# micro_schematic.net
KiCad netlist of a schematic drawn in EAGLE
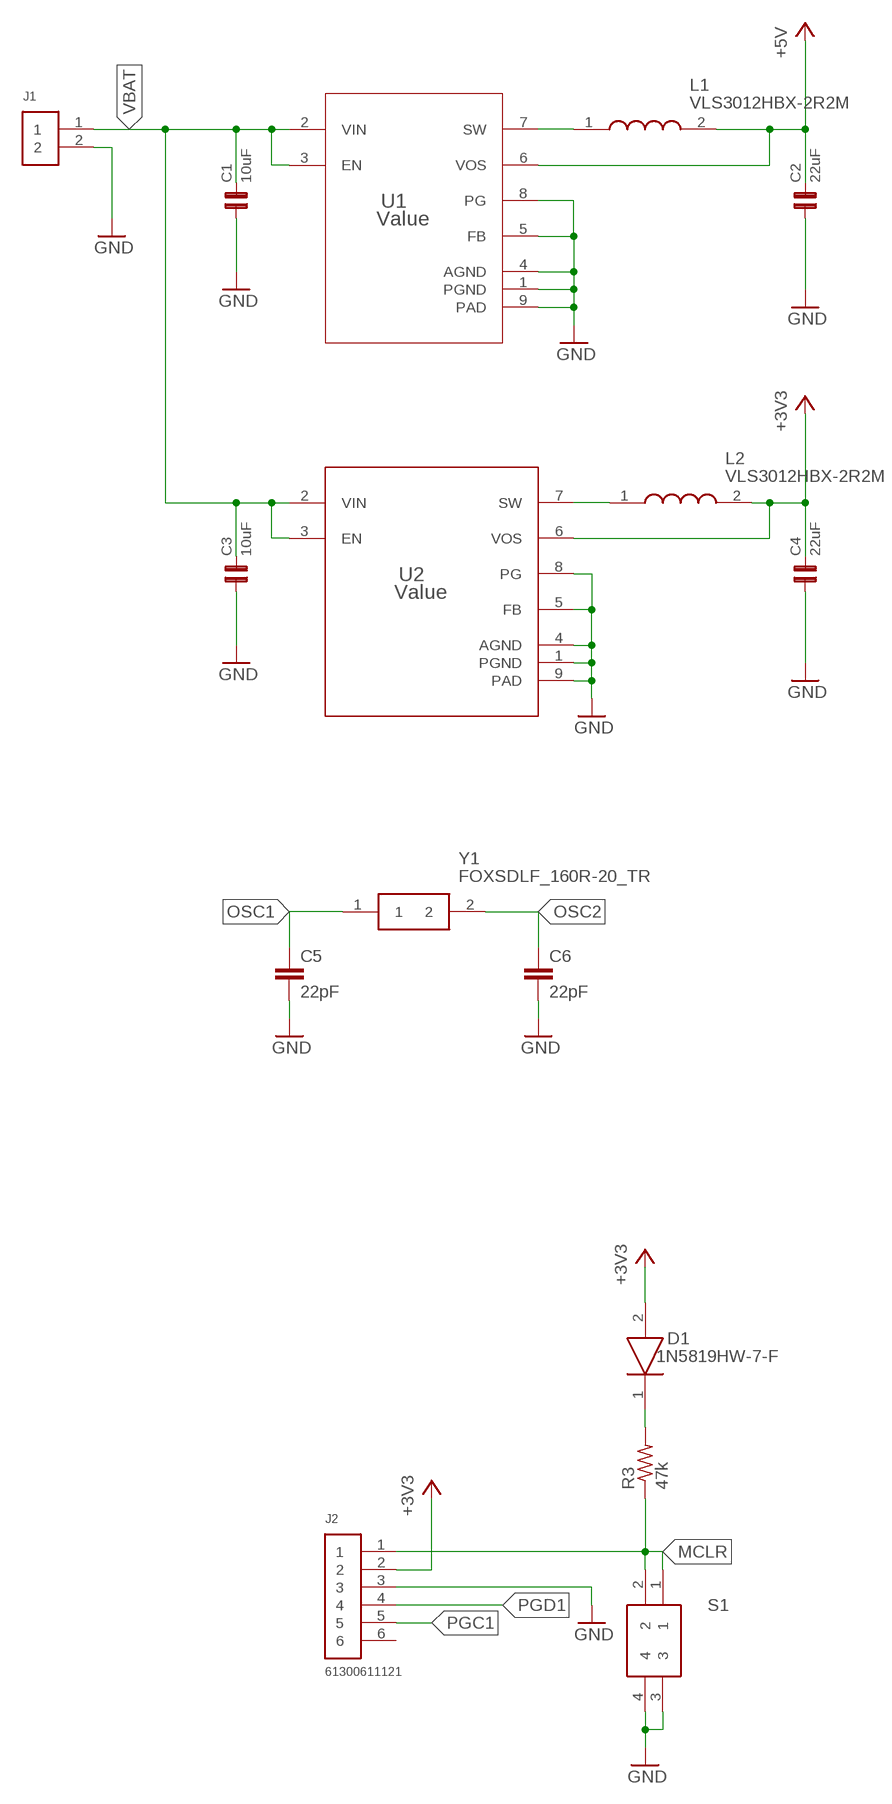
[diagram p0: schematic, sheet 1, part 1 of 2]
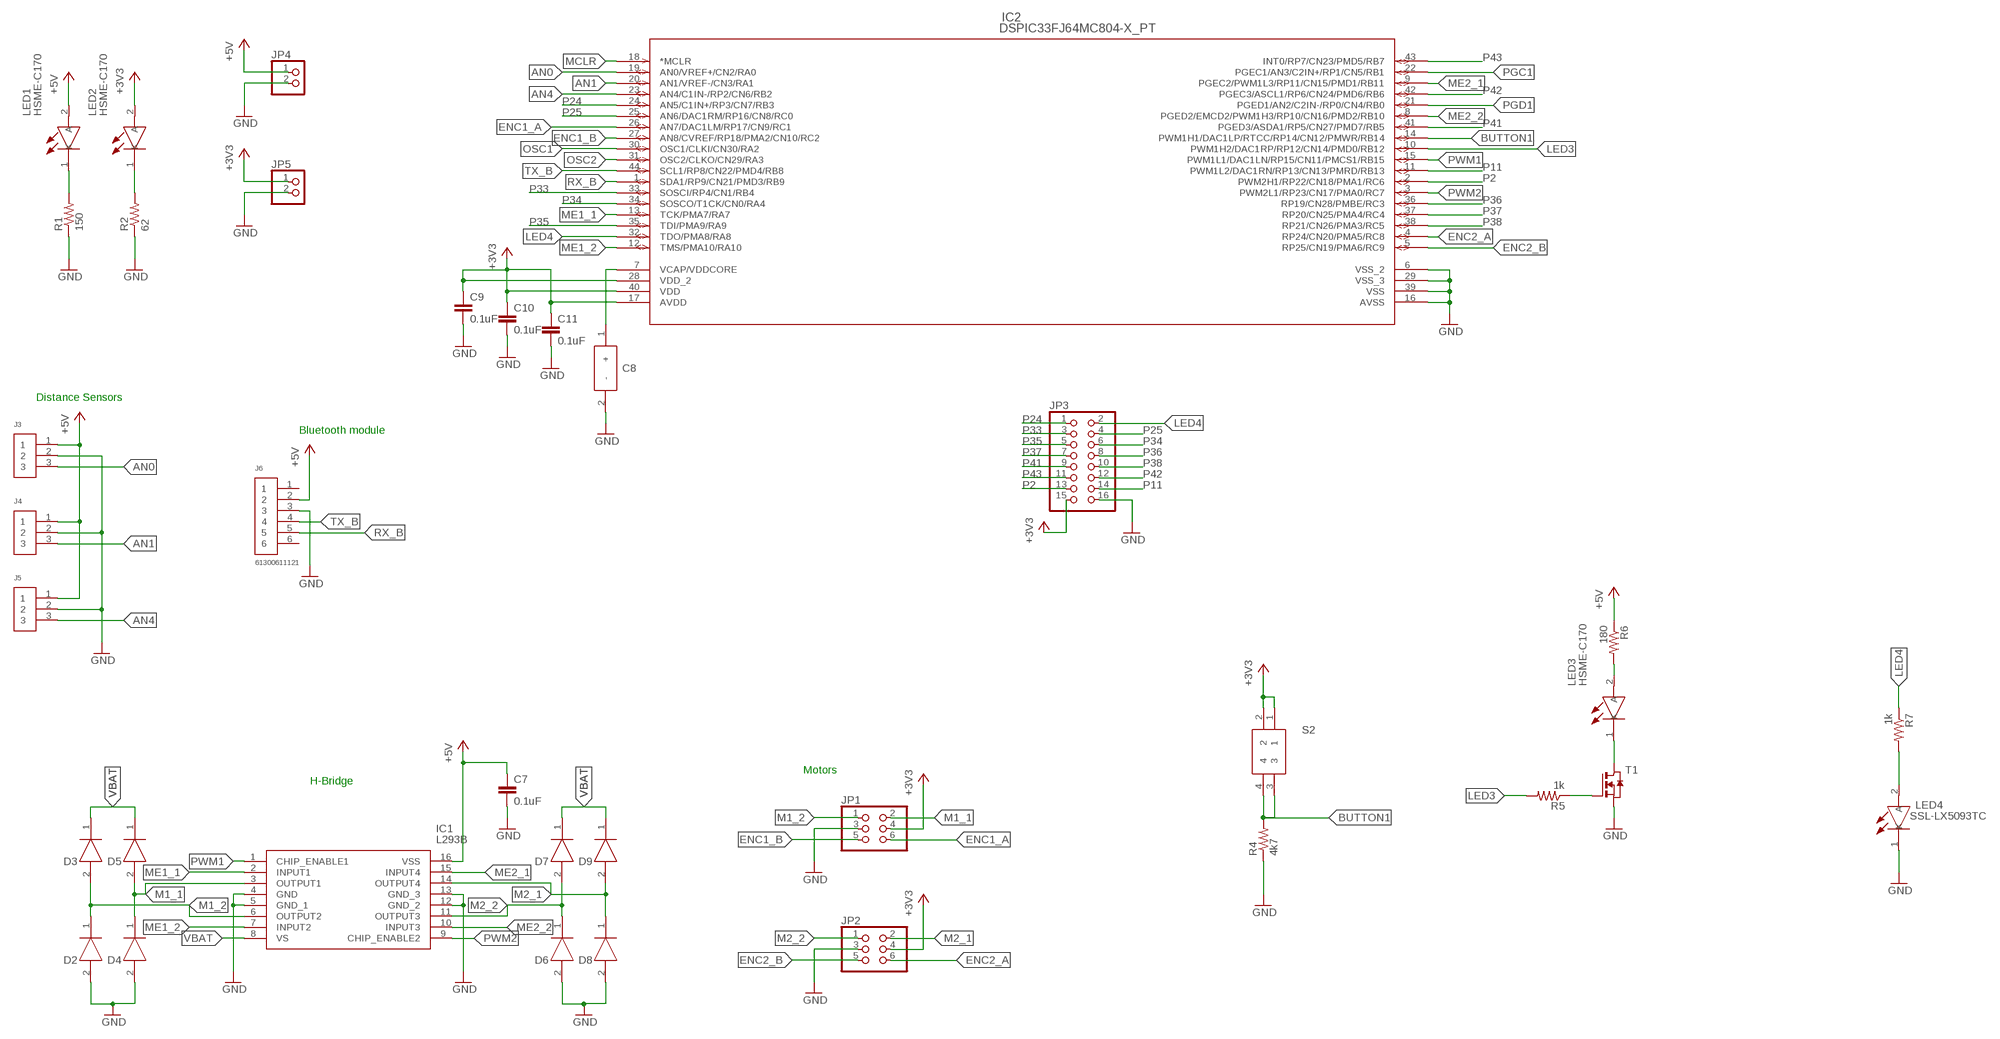
[diagram p1: schematic, sheet 1, part 2 of 2]

(export (version "E")
  (design (tool "Eeschema 10.0.6"))
  (components
    (comp (ref "C1")
      (value "10uF")
      (footprint "eagle-import:0805")
      (libsource (lib "eagle-import") (part "C0805"))
    )
    (comp (ref "C2")
      (value "22uF")
      (footprint "eagle-import:0805")
      (libsource (lib "eagle-import") (part "C0805"))
    )
    (comp (ref "C3")
      (value "10uF")
      (footprint "eagle-import:0805")
      (libsource (lib "eagle-import") (part "C0805"))
    )
    (comp (ref "C4")
      (value "22uF")
      (footprint "eagle-import:0805")
      (libsource (lib "eagle-import") (part "C0805"))
    )
    (comp (ref "C5")
      (value "22pF")
      (footprint "eagle-import:C0805")
      (libsource (lib "eagle-import") (part "C-EUC0805"))
    )
    (comp (ref "C6")
      (value "22pF")
      (footprint "eagle-import:C0805")
      (libsource (lib "eagle-import") (part "C-EUC0805"))
    )
    (comp (ref "C7")
      (value "0.1uF")
      (footprint "eagle-import:C0805")
      (libsource (lib "eagle-import") (part "C-EUC0805"))
    )
    (comp (ref "C8")
      (value "TPSB106K025T1800")
      (footprint "eagle-import:DIONM3528X210N")
      (fields (field (name "MOUSER_PART_NUMBER") "581-TPSB106K025T1800"))
      (libsource (lib "eagle-import") (part "TPSB106K025T1800"))
    )
    (comp (ref "C9")
      (value "0.1uF")
      (footprint "eagle-import:C0805")
      (libsource (lib "eagle-import") (part "C-EUC0805"))
    )
    (comp (ref "C10")
      (value "0.1uF")
      (footprint "eagle-import:C0805")
      (libsource (lib "eagle-import") (part "C-EUC0805"))
    )
    (comp (ref "C11")
      (value "0.1uF")
      (footprint "eagle-import:C0805")
      (libsource (lib "eagle-import") (part "C-EUC0805"))
    )
    (comp (ref "D1")
      (value "1N5819HW-7-F")
      (footprint "eagle-import:SOD3716X145N")
      (fields (field (name "MOUSER_PART_NUMBER") "621-1N5819HW-F"))
      (libsource (lib "eagle-import") (part "1N5819HW-7-F"))
    )
    (comp (ref "D2")
      (value "1N5819HW-7-F")
      (footprint "eagle-import:SOD3716X145N")
      (fields (field (name "MOUSER_PART_NUMBER") "621-1N5819HW-F"))
      (libsource (lib "eagle-import") (part "1N5819HW-7-F"))
    )
    (comp (ref "D3")
      (value "1N5819HW-7-F")
      (footprint "eagle-import:SOD3716X145N")
      (fields (field (name "MOUSER_PART_NUMBER") "621-1N5819HW-F"))
      (libsource (lib "eagle-import") (part "1N5819HW-7-F"))
    )
    (comp (ref "D4")
      (value "1N5819HW-7-F")
      (footprint "eagle-import:SOD3716X145N")
      (fields (field (name "MOUSER_PART_NUMBER") "621-1N5819HW-F"))
      (libsource (lib "eagle-import") (part "1N5819HW-7-F"))
    )
    (comp (ref "D5")
      (value "1N5819HW-7-F")
      (footprint "eagle-import:SOD3716X145N")
      (fields (field (name "MOUSER_PART_NUMBER") "621-1N5819HW-F"))
      (libsource (lib "eagle-import") (part "1N5819HW-7-F"))
    )
    (comp (ref "D6")
      (value "1N5819HW-7-F")
      (footprint "eagle-import:SOD3716X145N")
      (fields (field (name "MOUSER_PART_NUMBER") "621-1N5819HW-F"))
      (libsource (lib "eagle-import") (part "1N5819HW-7-F"))
    )
    (comp (ref "D7")
      (value "1N5819HW-7-F")
      (footprint "eagle-import:SOD3716X145N")
      (fields (field (name "MOUSER_PART_NUMBER") "621-1N5819HW-F"))
      (libsource (lib "eagle-import") (part "1N5819HW-7-F"))
    )
    (comp (ref "D8")
      (value "1N5819HW-7-F")
      (footprint "eagle-import:SOD3716X145N")
      (fields (field (name "MOUSER_PART_NUMBER") "621-1N5819HW-F"))
      (libsource (lib "eagle-import") (part "1N5819HW-7-F"))
    )
    (comp (ref "D9")
      (value "1N5819HW-7-F")
      (footprint "eagle-import:SOD3716X145N")
      (fields (field (name "MOUSER_PART_NUMBER") "621-1N5819HW-F"))
      (libsource (lib "eagle-import") (part "1N5819HW-7-F"))
    )
    (comp (ref "IC1")
      (value "L293B")
      (footprint "eagle-import:DIP780W50P254L2000H510Q16N")
      (fields (field (name "MOUSER_PART_NUMBER") "511-L293B"))
      (libsource (lib "eagle-import") (part "L293B"))
    )
    (comp (ref "IC2")
      (value "DSPIC33FJ64MC804-X_PT")
      (footprint "eagle-import:TQFP44_10X10MC")
      (libsource (lib "eagle-import") (part "DSPIC33FJ64MC804-X_PT"))
    )
    (comp (ref "J1")
      (value "61300211121")
      (footprint "eagle-import:61300211121")
      (fields
        (field (name "DIGI_KEY_PART_NUMBER") "732-5315-ND")
        (field (name "MANUFACTURER") "Wurth Electronics Inc.")
        (field (name "CREATED_BY") "PCBLayout.com")
      )
      (libsource (lib "eagle-import") (part "61300211121"))
    )
    (comp (ref "J2")
      (value "61300611121")
      (footprint "eagle-import:61300611121")
      (fields
        (field (name "DIGI_KEY_PART_NUMBER") "732-5319-ND")
        (field (name "MANUFACTURER") "Wurth Electronics Inc.")
        (field (name "CREATED_BY") "PCBLayout.com")
      )
      (libsource (lib "eagle-import") (part "61300611121"))
    )
    (comp (ref "J3")
      (value "61300311121")
      (footprint "eagle-import:61300311121")
      (fields
        (field (name "DIGI_KEY_PART_NUMBER") "732-5316-ND")
        (field (name "MANUFACTURER") "Wurth Electronics Inc.")
        (field (name "CREATED_BY") "PCBLayout.com")
      )
      (libsource (lib "eagle-import") (part "61300311121"))
    )
    (comp (ref "J4")
      (value "61300311121")
      (footprint "eagle-import:61300311121")
      (fields
        (field (name "DIGI_KEY_PART_NUMBER") "732-5316-ND")
        (field (name "MANUFACTURER") "Wurth Electronics Inc.")
        (field (name "CREATED_BY") "PCBLayout.com")
      )
      (libsource (lib "eagle-import") (part "61300311121"))
    )
    (comp (ref "J5")
      (value "61300311121")
      (footprint "eagle-import:61300311121")
      (fields
        (field (name "DIGI_KEY_PART_NUMBER") "732-5316-ND")
        (field (name "MANUFACTURER") "Wurth Electronics Inc.")
        (field (name "CREATED_BY") "PCBLayout.com")
      )
      (libsource (lib "eagle-import") (part "61300311121"))
    )
    (comp (ref "J6")
      (value "61300611121")
      (footprint "eagle-import:61300611121")
      (fields
        (field (name "DIGI_KEY_PART_NUMBER") "732-5319-ND")
        (field (name "MANUFACTURER") "Wurth Electronics Inc.")
        (field (name "CREATED_BY") "PCBLayout.com")
      )
      (libsource (lib "eagle-import") (part "61300611121"))
    )
    (comp (ref "JP1")
      (value "PINHD-2X3")
      (footprint "eagle-import:2X03")
      (libsource (lib "eagle-import") (part "PINHD-2X3"))
    )
    (comp (ref "JP2")
      (value "PINHD-2X3")
      (footprint "eagle-import:2X03")
      (libsource (lib "eagle-import") (part "PINHD-2X3"))
    )
    (comp (ref "JP3")
      (value "PINHD-2X8")
      (footprint "eagle-import:2X08")
      (libsource (lib "eagle-import") (part "PINHD-2X8"))
    )
    (comp (ref "JP4")
      (value "PINHD-1X2")
      (footprint "eagle-import:1X02")
      (libsource (lib "eagle-import") (part "PINHD-1X2"))
    )
    (comp (ref "JP5")
      (value "PINHD-1X2")
      (footprint "eagle-import:1X02")
      (libsource (lib "eagle-import") (part "PINHD-1X2"))
    )
    (comp (ref "L1")
      (value "VLS3012HBX-2R2M")
      (footprint "eagle-import:INDPM3030X120N")
      (fields (field (name "MOUSER_PART_NUMBER") "810-VLS3012HBX-2R2M"))
      (libsource (lib "eagle-import") (part "VLS3012HBX-2R2M"))
    )
    (comp (ref "L2")
      (value "VLS3012HBX-2R2M")
      (footprint "eagle-import:INDPM3030X120N")
      (fields (field (name "MOUSER_PART_NUMBER") "810-VLS3012HBX-2R2M"))
      (libsource (lib "eagle-import") (part "VLS3012HBX-2R2M"))
    )
    (comp (ref "LED1")
      (value "HSME-C170")
      (footprint "eagle-import:LEDC2012X90N")
      (fields (field (name "MOUSER_PART_NUMBER") "630-HSME-C170"))
      (libsource (lib "eagle-import") (part "HSME-C170"))
    )
    (comp (ref "LED2")
      (value "HSME-C170")
      (footprint "eagle-import:LEDC2012X90N")
      (fields (field (name "MOUSER_PART_NUMBER") "630-HSME-C170"))
      (libsource (lib "eagle-import") (part "HSME-C170"))
    )
    (comp (ref "LED3")
      (value "HSME-C170")
      (footprint "eagle-import:LEDC2012X90N")
      (fields (field (name "MOUSER_PART_NUMBER") "630-HSME-C170"))
      (libsource (lib "eagle-import") (part "HSME-C170"))
    )
    (comp (ref "LED4")
      (value "SSL-LX5093TC")
      (footprint "eagle-import:SSL-LX5093SGC_B")
      (fields (field (name "MOUSER_PART_NUMBER") "696-SSL-LX5093TC"))
      (libsource (lib "eagle-import") (part "SSL-LX5093TC"))
    )
    (comp (ref "R1")
      (value "150")
      (footprint "eagle-import:R0805")
      (libsource (lib "eagle-import") (part "R-US_R0805"))
    )
    (comp (ref "R2")
      (value "62")
      (footprint "eagle-import:R0805")
      (libsource (lib "eagle-import") (part "R-US_R0805"))
    )
    (comp (ref "R3")
      (value "47k")
      (footprint "eagle-import:R0805")
      (libsource (lib "eagle-import") (part "R-US_R0805"))
    )
    (comp (ref "R4")
      (value "4k7")
      (footprint "eagle-import:R0805")
      (libsource (lib "eagle-import") (part "R-US_R0805"))
    )
    (comp (ref "R5")
      (value "1k")
      (footprint "eagle-import:R0805")
      (libsource (lib "eagle-import") (part "R-US_R0805"))
    )
    (comp (ref "R6")
      (value "180")
      (footprint "eagle-import:R0805")
      (libsource (lib "eagle-import") (part "R-US_R0805"))
    )
    (comp (ref "R7")
      (value "1k")
      (footprint "eagle-import:R0805")
      (libsource (lib "eagle-import") (part "R-US_R0805"))
    )
    (comp (ref "S1")
      (value "PTS647SM50SMTR2LFS")
      (footprint "eagle-import:PTS647SM50SMTR2LFS")
      (fields (field (name "MOUSER_PART_NUMBER") "611-PTS647SM50SMTR2L"))
      (libsource (lib "eagle-import") (part "PTS647SM50SMTR2LFS"))
    )
    (comp (ref "S2")
      (value "PTS647SM50SMTR2LFS")
      (footprint "eagle-import:PTS647SM50SMTR2LFS")
      (fields (field (name "MOUSER_PART_NUMBER") "611-PTS647SM50SMTR2L"))
      (libsource (lib "eagle-import") (part "PTS647SM50SMTR2LFS"))
    )
    (comp (ref "T1")
      (value "NMOSSOT23")
      (footprint "eagle-import:SOT-23")
      (libsource (lib "eagle-import") (part "NMOSSOT23"))
    )
    (comp (ref "U1")
      (value "Value")
      (footprint "eagle-import:DSG0008A")
      (fields
        (field (name "ALTERNATEPARTNUMBER") "TPS62163DSGT")
        (field (name "MANUFACTURER") "Texas Instruments")
        (field (name "PARTNUMBER") "TPS62163DSGR")
        (field (name "SPICEPREFIX") "X")
      )
      (libsource (lib "eagle-import") (part "TPS62163DSGR"))
    )
    (comp (ref "U2")
      (value "Value")
      (footprint "eagle-import:DSG0008A")
      (fields (field (name "MANUFACTURER") "Texas Instruments") (field (name "PARTNUMBER") "TPS62162QDSGRQ1"))
      (libsource (lib "eagle-import") (part "TPS62162QDSGRQ1"))
    )
    (comp (ref "Y1")
      (value "FOXSDLF_160R-20_TR")
      (footprint "eagle-import:FOXSDLF_240F-20")
      (fields
        (field (name "MANUFACTURER_PART_NUMBER") "FOXSDLF/160R-20/TR")
        (field (name "MOUSER_PART_NUMBER") "559-FOXSDLF/160R-20")
      )
      (libsource (lib "eagle-import") (part "FOXSDLF_160R-20_TR"))
    )
  )
  (nets
    (net (code "1") (name "+3V3") (class "Default")
      (node (ref "C10") (pin "1") (pinfunction "1_1") (pintype "passive"))
      (node (ref "C11") (pin "1") (pinfunction "1_1") (pintype "passive"))
      (node (ref "C4") (pin "2") (pinfunction "2_2") (pintype "passive"))
      (node (ref "C9") (pin "1") (pinfunction "1_1") (pintype "passive"))
      (node (ref "D1") (pin "2") (pinfunction "A_2") (pintype "bidirectional"))
      (node (ref "IC2") (pin "17") (pinfunction "AVDD_17") (pintype "power_in"))
      (node (ref "IC2") (pin "28") (pinfunction "VDD_2_28") (pintype "power_in"))
      (node (ref "IC2") (pin "40") (pinfunction "VDD_40") (pintype "power_in"))
      (node (ref "J2") (pin "2") (pinfunction "2_2") (pintype "passive"))
      (node (ref "JP1") (pin "4") (pinfunction "4_4") (pintype "passive"))
      (node (ref "JP2") (pin "4") (pinfunction "4_4") (pintype "passive"))
      (node (ref "JP3") (pin "15") (pinfunction "15_15") (pintype "passive"))
      (node (ref "JP5") (pin "1") (pinfunction "1_1") (pintype "passive"))
      (node (ref "L2") (pin "2") (pinfunction "2_2") (pintype "bidirectional"))
      (node (ref "LED2") (pin "2") (pinfunction "A_2") (pintype "bidirectional"))
      (node (ref "S2") (pin "1") (pinfunction "1_1") (pintype "bidirectional"))
      (node (ref "S2") (pin "2") (pinfunction "2_2") (pintype "bidirectional"))
      (node (ref "U2") (pin "6") (pinfunction "VOS_6") (pintype "input"))
    )
    (net (code "2") (name "+5V") (class "Default")
      (node (ref "C2") (pin "2") (pinfunction "2_2") (pintype "passive"))
      (node (ref "C7") (pin "1") (pinfunction "1_1") (pintype "passive"))
      (node (ref "IC1") (pin "16") (pinfunction "VSS_16") (pintype "power_in"))
      (node (ref "J3") (pin "1") (pinfunction "1_1") (pintype "passive"))
      (node (ref "J4") (pin "1") (pinfunction "1_1") (pintype "passive"))
      (node (ref "J5") (pin "1") (pinfunction "1_1") (pintype "passive"))
      (node (ref "J6") (pin "2") (pinfunction "2_2") (pintype "passive"))
      (node (ref "JP4") (pin "1") (pinfunction "1_1") (pintype "passive"))
      (node (ref "L1") (pin "2") (pinfunction "2_2") (pintype "bidirectional"))
      (node (ref "LED1") (pin "2") (pinfunction "A_2") (pintype "bidirectional"))
      (node (ref "R6") (pin "1") (pinfunction "1_1") (pintype "passive"))
      (node (ref "U1") (pin "6") (pinfunction "VOS_6") (pintype "input"))
    )
    (net (code "3") (name "/P2") (class "Default")
      (node (ref "IC2") (pin "2") (pinfunction "PWM2H1/RP22/CN18/PMA1/RC6_2") (pintype "bidirectional"))
      (node (ref "JP3") (pin "13") (pinfunction "13_13") (pintype "passive"))
    )
    (net (code "4") (name "/P11") (class "Default")
      (node (ref "IC2") (pin "11") (pinfunction "PWM1L2/DAC1RN/RP13/CN13/PMRD/RB13_11") (pintype "bidirectional"))
      (node (ref "JP3") (pin "14") (pinfunction "14_14") (pintype "passive"))
    )
    (net (code "5") (name "/P24") (class "Default")
      (node (ref "IC2") (pin "24") (pinfunction "AN5/C1IN+/RP3/CN7/RB3_24") (pintype "bidirectional"))
      (node (ref "JP3") (pin "1") (pinfunction "1_1") (pintype "passive"))
    )
    (net (code "6") (name "/P25") (class "Default")
      (node (ref "IC2") (pin "25") (pinfunction "AN6/DAC1RM/RP16/CN8/RC0_25") (pintype "bidirectional"))
      (node (ref "JP3") (pin "4") (pinfunction "4_4") (pintype "passive"))
    )
    (net (code "7") (name "/P33") (class "Default")
      (node (ref "IC2") (pin "33") (pinfunction "SOSCI/RP4/CN1/RB4_33") (pintype "bidirectional"))
      (node (ref "JP3") (pin "3") (pinfunction "3_3") (pintype "passive"))
    )
    (net (code "8") (name "/P34") (class "Default")
      (node (ref "IC2") (pin "34") (pinfunction "SOSCO/T1CK/CN0/RA4_34") (pintype "bidirectional"))
      (node (ref "JP3") (pin "6") (pinfunction "6_6") (pintype "passive"))
    )
    (net (code "9") (name "/P35") (class "Default")
      (node (ref "IC2") (pin "35") (pinfunction "TDI/PMA9/RA9_35") (pintype "bidirectional"))
      (node (ref "JP3") (pin "5") (pinfunction "5_5") (pintype "passive"))
    )
    (net (code "10") (name "/P36") (class "Default")
      (node (ref "IC2") (pin "36") (pinfunction "RP19/CN28/PMBE/RC3_36") (pintype "bidirectional"))
      (node (ref "JP3") (pin "8") (pinfunction "8_8") (pintype "passive"))
    )
    (net (code "11") (name "/P37") (class "Default")
      (node (ref "IC2") (pin "37") (pinfunction "RP20/CN25/PMA4/RC4_37") (pintype "bidirectional"))
      (node (ref "JP3") (pin "7") (pinfunction "7_7") (pintype "passive"))
    )
    (net (code "12") (name "/P38") (class "Default")
      (node (ref "IC2") (pin "38") (pinfunction "RP21/CN26/PMA3/RC5_38") (pintype "bidirectional"))
      (node (ref "JP3") (pin "10") (pinfunction "10_10") (pintype "passive"))
    )
    (net (code "13") (name "/P41") (class "Default")
      (node (ref "IC2") (pin "41") (pinfunction "PGED3/ASDA1/RP5/CN27/PMD7/RB5_41") (pintype "bidirectional"))
      (node (ref "JP3") (pin "9") (pinfunction "9_9") (pintype "passive"))
    )
    (net (code "14") (name "/P42") (class "Default")
      (node (ref "IC2") (pin "42") (pinfunction "PGEC3/ASCL1/RP6/CN24/PMD6/RB6_42") (pintype "bidirectional"))
      (node (ref "JP3") (pin "12") (pinfunction "12_12") (pintype "passive"))
    )
    (net (code "15") (name "/P43") (class "Default")
      (node (ref "IC2") (pin "43") (pinfunction "INT0/RP7/CN23/PMD5/RB7_43") (pintype "bidirectional"))
      (node (ref "JP3") (pin "11") (pinfunction "11_11") (pintype "passive"))
    )
    (net (code "16") (name "AN0") (class "Default")
      (node (ref "IC2") (pin "19") (pinfunction "AN0/VREF+/CN2/RA0_19") (pintype "bidirectional"))
      (node (ref "J3") (pin "3") (pinfunction "3_3") (pintype "passive"))
    )
    (net (code "17") (name "AN1") (class "Default")
      (node (ref "IC2") (pin "20") (pinfunction "AN1/VREF-/CN3/RA1_20") (pintype "bidirectional"))
      (node (ref "J4") (pin "3") (pinfunction "3_3") (pintype "passive"))
    )
    (net (code "18") (name "AN4") (class "Default")
      (node (ref "IC2") (pin "23") (pinfunction "AN4/C1IN-/RP2/CN6/RB2_23") (pintype "bidirectional"))
      (node (ref "J5") (pin "3") (pinfunction "3_3") (pintype "passive"))
    )
    (net (code "19") (name "BUTTON1") (class "Default")
      (node (ref "IC2") (pin "14") (pinfunction "PWM1H1/DAC1LP/RTCC/RP14/CN12/PMWR/RB14_14") (pintype "bidirectional"))
      (node (ref "R4") (pin "2") (pinfunction "2_2") (pintype "passive"))
      (node (ref "S2") (pin "3") (pinfunction "3_3") (pintype "bidirectional"))
      (node (ref "S2") (pin "4") (pinfunction "4_4") (pintype "bidirectional"))
    )
    (net (code "20") (name "ENC1_A") (class "Default")
      (node (ref "IC2") (pin "26") (pinfunction "AN7/DAC1LM/RP17/CN9/RC1_26") (pintype "bidirectional"))
      (node (ref "JP1") (pin "6") (pinfunction "6_6") (pintype "passive"))
    )
    (net (code "21") (name "ENC1_B") (class "Default")
      (node (ref "IC2") (pin "27") (pinfunction "AN8/CVREF/RP18/PMA2/CN10/RC2_27") (pintype "bidirectional"))
      (node (ref "JP1") (pin "5") (pinfunction "5_5") (pintype "passive"))
    )
    (net (code "22") (name "ENC2_A") (class "Default")
      (node (ref "IC2") (pin "4") (pinfunction "RP24/CN20/PMA5/RC8_4") (pintype "bidirectional"))
      (node (ref "JP2") (pin "6") (pinfunction "6_6") (pintype "passive"))
    )
    (net (code "23") (name "ENC2_B") (class "Default")
      (node (ref "IC2") (pin "5") (pinfunction "RP25/CN19/PMA6/RC9_5") (pintype "bidirectional"))
      (node (ref "JP2") (pin "5") (pinfunction "5_5") (pintype "passive"))
    )
    (net (code "24") (name "GND") (class "Default")
      (node (ref "C1") (pin "1") (pinfunction "1_1") (pintype "passive"))
      (node (ref "C10") (pin "2") (pinfunction "2_2") (pintype "passive"))
      (node (ref "C11") (pin "2") (pinfunction "2_2") (pintype "passive"))
      (node (ref "C2") (pin "1") (pinfunction "1_1") (pintype "passive"))
      (node (ref "C3") (pin "1") (pinfunction "1_1") (pintype "passive"))
      (node (ref "C4") (pin "1") (pinfunction "1_1") (pintype "passive"))
      (node (ref "C5") (pin "2") (pinfunction "2_2") (pintype "passive"))
      (node (ref "C6") (pin "2") (pinfunction "2_2") (pintype "passive"))
      (node (ref "C7") (pin "2") (pinfunction "2_2") (pintype "passive"))
      (node (ref "C8") (pin "2") (pinfunction "-_2") (pintype "bidirectional"))
      (node (ref "C9") (pin "2") (pinfunction "2_2") (pintype "passive"))
      (node (ref "D2") (pin "2") (pinfunction "A_2") (pintype "bidirectional"))
      (node (ref "D4") (pin "2") (pinfunction "A_2") (pintype "bidirectional"))
      (node (ref "D6") (pin "2") (pinfunction "A_2") (pintype "bidirectional"))
      (node (ref "D8") (pin "2") (pinfunction "A_2") (pintype "bidirectional"))
      (node (ref "IC1") (pin "12") (pinfunction "GND_2_12") (pintype "power_in"))
      (node (ref "IC1") (pin "13") (pinfunction "GND_3_13") (pintype "power_in"))
      (node (ref "IC1") (pin "4") (pinfunction "GND_4") (pintype "power_in"))
      (node (ref "IC1") (pin "5") (pinfunction "GND_1_5") (pintype "power_in"))
      (node (ref "IC2") (pin "16") (pinfunction "AVSS_16") (pintype "power_in"))
      (node (ref "IC2") (pin "29") (pinfunction "VSS_3_29") (pintype "power_in"))
      (node (ref "IC2") (pin "39") (pinfunction "VSS_39") (pintype "power_in"))
      (node (ref "IC2") (pin "6") (pinfunction "VSS_2_6") (pintype "power_in"))
      (node (ref "J1") (pin "2") (pinfunction "2_2") (pintype "passive"))
      (node (ref "J2") (pin "3") (pinfunction "3_3") (pintype "passive"))
      (node (ref "J3") (pin "2") (pinfunction "2_2") (pintype "passive"))
      (node (ref "J4") (pin "2") (pinfunction "2_2") (pintype "passive"))
      (node (ref "J5") (pin "2") (pinfunction "2_2") (pintype "passive"))
      (node (ref "J6") (pin "3") (pinfunction "3_3") (pintype "passive"))
      (node (ref "JP1") (pin "3") (pinfunction "3_3") (pintype "passive"))
      (node (ref "JP2") (pin "3") (pinfunction "3_3") (pintype "passive"))
      (node (ref "JP3") (pin "16") (pinfunction "16_16") (pintype "passive"))
      (node (ref "JP4") (pin "2") (pinfunction "2_2") (pintype "passive"))
      (node (ref "JP5") (pin "2") (pinfunction "2_2") (pintype "passive"))
      (node (ref "LED4") (pin "1") (pinfunction "K_1") (pintype "bidirectional"))
      (node (ref "R1") (pin "1") (pinfunction "1_1") (pintype "passive"))
      (node (ref "R2") (pin "1") (pinfunction "1_1") (pintype "passive"))
      (node (ref "R4") (pin "1") (pinfunction "1_1") (pintype "passive"))
      (node (ref "S1") (pin "3") (pinfunction "3_3") (pintype "bidirectional"))
      (node (ref "S1") (pin "4") (pinfunction "4_4") (pintype "bidirectional"))
      (node (ref "T1") (pin "2") (pinfunction "S_2") (pintype "passive"))
      (node (ref "U1") (pin "1") (pinfunction "PGND_1") (pintype "power_in"))
      (node (ref "U1") (pin "4") (pinfunction "AGND_4") (pintype "power_in"))
      (node (ref "U1") (pin "5") (pinfunction "FB_5") (pintype "input"))
      (node (ref "U1") (pin "8") (pinfunction "PG_8") (pintype "tri_state"))
      (node (ref "U1") (pin "9") (pinfunction "PAD_9") (pintype "power_in"))
      (node (ref "U2") (pin "1") (pinfunction "PGND_1") (pintype "power_in"))
      (node (ref "U2") (pin "4") (pinfunction "AGND_4") (pintype "power_in"))
      (node (ref "U2") (pin "5") (pinfunction "FB_5") (pintype "input"))
      (node (ref "U2") (pin "8") (pinfunction "PG_8") (pintype "tri_state"))
      (node (ref "U2") (pin "9") (pinfunction "PAD_9") (pintype "power_in"))
    )
    (net (code "25") (name "LED3") (class "Default")
      (node (ref "IC2") (pin "10") (pinfunction "PWM1H2/DAC1RP/RP12/CN14/PMD0/RB12_10") (pintype "bidirectional"))
      (node (ref "R5") (pin "2") (pinfunction "2_2") (pintype "passive"))
    )
    (net (code "26") (name "LED4") (class "Default")
      (node (ref "IC2") (pin "32") (pinfunction "TDO/PMA8/RA8_32") (pintype "bidirectional"))
      (node (ref "JP3") (pin "2") (pinfunction "2_2") (pintype "passive"))
      (node (ref "R7") (pin "1") (pinfunction "1_1") (pintype "passive"))
    )
    (net (code "27") (name "M1_1") (class "Default")
      (node (ref "D4") (pin "1") (pinfunction "K_1") (pintype "bidirectional"))
      (node (ref "D5") (pin "2") (pinfunction "A_2") (pintype "bidirectional"))
      (node (ref "IC1") (pin "3") (pinfunction "OUTPUT1_3") (pintype "output"))
      (node (ref "JP1") (pin "2") (pinfunction "2_2") (pintype "passive"))
    )
    (net (code "28") (name "M1_2") (class "Default")
      (node (ref "D2") (pin "1") (pinfunction "K_1") (pintype "bidirectional"))
      (node (ref "D3") (pin "2") (pinfunction "A_2") (pintype "bidirectional"))
      (node (ref "IC1") (pin "6") (pinfunction "OUTPUT2_6") (pintype "output"))
      (node (ref "JP1") (pin "1") (pinfunction "1_1") (pintype "passive"))
    )
    (net (code "29") (name "M2_1") (class "Default")
      (node (ref "D8") (pin "1") (pinfunction "K_1") (pintype "bidirectional"))
      (node (ref "D9") (pin "2") (pinfunction "A_2") (pintype "bidirectional"))
      (node (ref "IC1") (pin "14") (pinfunction "OUTPUT4_14") (pintype "output"))
      (node (ref "JP2") (pin "2") (pinfunction "2_2") (pintype "passive"))
    )
    (net (code "30") (name "M2_2") (class "Default")
      (node (ref "D6") (pin "1") (pinfunction "K_1") (pintype "bidirectional"))
      (node (ref "D7") (pin "2") (pinfunction "A_2") (pintype "bidirectional"))
      (node (ref "IC1") (pin "11") (pinfunction "OUTPUT3_11") (pintype "output"))
      (node (ref "JP2") (pin "1") (pinfunction "1_1") (pintype "passive"))
    )
    (net (code "31") (name "MCLR") (class "Default")
      (node (ref "IC2") (pin "18") (pinfunction "*MCLR_18") (pintype "input"))
      (node (ref "J2") (pin "1") (pinfunction "1_1") (pintype "passive"))
      (node (ref "R3") (pin "1") (pinfunction "1_1") (pintype "passive"))
      (node (ref "S1") (pin "1") (pinfunction "1_1") (pintype "bidirectional"))
      (node (ref "S1") (pin "2") (pinfunction "2_2") (pintype "bidirectional"))
    )
    (net (code "32") (name "ME1_1") (class "Default")
      (node (ref "IC1") (pin "2") (pinfunction "INPUT1_2") (pintype "input"))
      (node (ref "IC2") (pin "13") (pinfunction "TCK/PMA7/RA7_13") (pintype "bidirectional"))
    )
    (net (code "33") (name "ME1_2") (class "Default")
      (node (ref "IC1") (pin "7") (pinfunction "INPUT2_7") (pintype "input"))
      (node (ref "IC2") (pin "12") (pinfunction "TMS/PMA10/RA10_12") (pintype "bidirectional"))
    )
    (net (code "34") (name "ME2_1") (class "Default")
      (node (ref "IC1") (pin "15") (pinfunction "INPUT4_15") (pintype "input"))
      (node (ref "IC2") (pin "9") (pinfunction "PGEC2/PWM1L3/RP11/CN15/PMD1/RB11_9") (pintype "bidirectional"))
    )
    (net (code "35") (name "ME2_2") (class "Default")
      (node (ref "IC1") (pin "10") (pinfunction "INPUT3_10") (pintype "input"))
      (node (ref "IC2") (pin "8") (pinfunction "PGED2/EMCD2/PWM1H3/RP10/CN16/PMD2/RB10_8") (pintype "bidirectional"))
    )
    (net (code "36") (name "Net-(C8-+)") (class "Default")
      (node (ref "C8") (pin "1") (pinfunction "+_1") (pintype "bidirectional"))
      (node (ref "IC2") (pin "7") (pinfunction "VCAP/VDDCORE_7") (pintype "power_in"))
    )
    (net (code "37") (name "Net-(D1-K)") (class "Default")
      (node (ref "D1") (pin "1") (pinfunction "K_1") (pintype "bidirectional"))
      (node (ref "R3") (pin "2") (pinfunction "2_2") (pintype "passive"))
    )
    (net (code "38") (name "Net-(LED1-K)") (class "Default")
      (node (ref "LED1") (pin "1") (pinfunction "K_1") (pintype "bidirectional"))
      (node (ref "R1") (pin "2") (pinfunction "2_2") (pintype "passive"))
    )
    (net (code "39") (name "Net-(LED2-K)") (class "Default")
      (node (ref "LED2") (pin "1") (pinfunction "K_1") (pintype "bidirectional"))
      (node (ref "R2") (pin "2") (pinfunction "2_2") (pintype "passive"))
    )
    (net (code "40") (name "Net-(LED3-A)") (class "Default")
      (node (ref "LED3") (pin "2") (pinfunction "A_2") (pintype "bidirectional"))
      (node (ref "R6") (pin "2") (pinfunction "2_2") (pintype "passive"))
    )
    (net (code "41") (name "Net-(LED3-K)") (class "Default")
      (node (ref "LED3") (pin "1") (pinfunction "K_1") (pintype "bidirectional"))
      (node (ref "T1") (pin "1") (pinfunction "D_1") (pintype "passive"))
    )
    (net (code "42") (name "Net-(LED4-A)") (class "Default")
      (node (ref "LED4") (pin "2") (pinfunction "A_2") (pintype "bidirectional"))
      (node (ref "R7") (pin "2") (pinfunction "2_2") (pintype "passive"))
    )
    (net (code "43") (name "Net-(T1-G)") (class "Default")
      (node (ref "R5") (pin "1") (pinfunction "1_1") (pintype "passive"))
      (node (ref "T1") (pin "3") (pinfunction "G_3") (pintype "passive"))
    )
    (net (code "44") (name "Net-(U1-SW)") (class "Default")
      (node (ref "L1") (pin "1") (pinfunction "1_1") (pintype "bidirectional"))
      (node (ref "U1") (pin "7") (pinfunction "SW_7") (pintype "power_in"))
    )
    (net (code "45") (name "Net-(U2-SW)") (class "Default")
      (node (ref "L2") (pin "1") (pinfunction "1_1") (pintype "bidirectional"))
      (node (ref "U2") (pin "7") (pinfunction "SW_7") (pintype "power_in"))
    )
    (net (code "46") (name "OSC1") (class "Default")
      (node (ref "C5") (pin "1") (pinfunction "1_1") (pintype "passive"))
      (node (ref "IC2") (pin "30") (pinfunction "OSC1/CLKI/CN30/RA2_30") (pintype "bidirectional"))
      (node (ref "Y1") (pin "1") (pinfunction "1_1") (pintype "bidirectional"))
    )
    (net (code "47") (name "OSC2") (class "Default")
      (node (ref "C6") (pin "1") (pinfunction "1_1") (pintype "passive"))
      (node (ref "IC2") (pin "31") (pinfunction "OSC2/CLKO/CN29/RA3_31") (pintype "bidirectional"))
      (node (ref "Y1") (pin "2") (pinfunction "2_2") (pintype "bidirectional"))
    )
    (net (code "48") (name "PGC1") (class "Default")
      (node (ref "IC2") (pin "22") (pinfunction "PGEC1/AN3/C2IN+/RP1/CN5/RB1_22") (pintype "bidirectional"))
      (node (ref "J2") (pin "5") (pinfunction "5_5") (pintype "passive"))
    )
    (net (code "49") (name "PGD1") (class "Default")
      (node (ref "IC2") (pin "21") (pinfunction "PGED1/AN2/C2IN-/RP0/CN4/RB0_21") (pintype "bidirectional"))
      (node (ref "J2") (pin "4") (pinfunction "4_4") (pintype "passive"))
    )
    (net (code "50") (name "PWM1") (class "Default")
      (node (ref "IC1") (pin "1") (pinfunction "CHIP_ENABLE1_1") (pintype "output"))
      (node (ref "IC2") (pin "15") (pinfunction "PWM1L1/DAC1LN/RP15/CN11/PMCS1/RB15_15") (pintype "bidirectional"))
    )
    (net (code "51") (name "PWM2") (class "Default")
      (node (ref "IC1") (pin "9") (pinfunction "CHIP_ENABLE2_9") (pintype "output"))
      (node (ref "IC2") (pin "3") (pinfunction "PWM2L1/RP23/CN17/PMA0/RC7_3") (pintype "bidirectional"))
    )
    (net (code "52") (name "RX_B") (class "Default")
      (node (ref "IC2") (pin "1") (pinfunction "SDA1/RP9/CN21/PMD3/RB9_1") (pintype "bidirectional"))
      (node (ref "J6") (pin "5") (pinfunction "5_5") (pintype "passive"))
    )
    (net (code "53") (name "TX_B") (class "Default")
      (node (ref "IC2") (pin "44") (pinfunction "SCL1/RP8/CN22/PMD4/RB8_44") (pintype "bidirectional"))
      (node (ref "J6") (pin "4") (pinfunction "4_4") (pintype "passive"))
    )
    (net (code "54") (name "VBAT") (class "Default")
      (node (ref "C1") (pin "2") (pinfunction "2_2") (pintype "passive"))
      (node (ref "C3") (pin "2") (pinfunction "2_2") (pintype "passive"))
      (node (ref "D3") (pin "1") (pinfunction "K_1") (pintype "bidirectional"))
      (node (ref "D5") (pin "1") (pinfunction "K_1") (pintype "bidirectional"))
      (node (ref "D7") (pin "1") (pinfunction "K_1") (pintype "bidirectional"))
      (node (ref "D9") (pin "1") (pinfunction "K_1") (pintype "bidirectional"))
      (node (ref "IC1") (pin "8") (pinfunction "VS_8") (pintype "power_in"))
      (node (ref "J1") (pin "1") (pinfunction "1_1") (pintype "passive"))
      (node (ref "U1") (pin "2") (pinfunction "VIN_2") (pintype "power_in"))
      (node (ref "U1") (pin "3") (pinfunction "EN_3") (pintype "input"))
      (node (ref "U2") (pin "2") (pinfunction "VIN_2") (pintype "power_in"))
      (node (ref "U2") (pin "3") (pinfunction "EN_3") (pintype "input"))
    )
    (net (code "55") (name "unconnected-(J2-Pad6)") (class "Default")
      (node (ref "J2") (pin "6") (pinfunction "6_6") (pintype "passive"))
    )
    (net (code "56") (name "unconnected-(J6-Pad1)") (class "Default")
      (node (ref "J6") (pin "1") (pinfunction "1_1") (pintype "passive"))
    )
    (net (code "57") (name "unconnected-(J6-Pad6)") (class "Default")
      (node (ref "J6") (pin "6") (pinfunction "6_6") (pintype "passive"))
    )
  )
)
